# RTC_ds1307z.net
KiCad netlist of a schematic drawn in Altium Designer
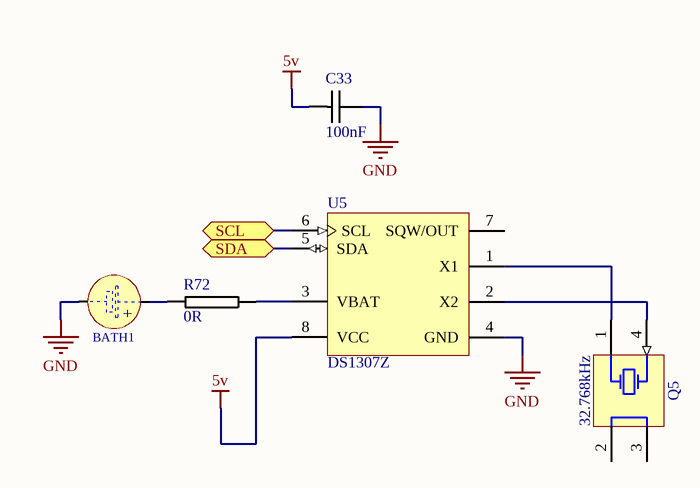
[diagram p0: RTC_ds1307z.SchDoc]

(export (version "E")
  (design (tool "Eeschema 10.0.6"))
  (components
    (comp (ref "BATH1")
      (value "~")
      (footprint "BATH_KEYSTONE_103")
      (description "Battery Holder whit 2 Pin")
      (fields
        (field (name "PART NUMBER") "BATH_KEYSTONE_103")
        (field (name "MANUFACTURER") "KEYSTONE")
        (field (name "AUTHOR") "CERN DEM JLC")
      )
      (libsource (lib "Eletro-mechanical") (part "Battery Holder 2 Pin"))
    )
    (comp (ref "C33")
      (value "100nF")
      (footprint "0805C-TBD")
      (description "CAPACITOR 0805 CERAMIC")
      (libsource (lib "vh_altium_library") (part "0805C-100nF-25V-X7R-MUR"))
    )
    (comp (ref "Q5")
      (value "32.768kHz")
      (footprint "XTAL_EPSON_MC-406")
      (description "Crystal 4 pins 1=XTAL Control 2 And 3=NC 4=XTAL")
      (fields
        (field (name "PART NUMBER") "XTAL_32.768KHZ_EPSON_MC-406 32.768K-A3:ROHS")
        (field (name "MANUFACTURER") "EPSON TOYOCOM")
        (field (name "AUTHOR") "CERN DEM JLC")
      )
      (libsource (lib "ICs And Semiconductors") (part "Quartz Crystal 1X 2-3NC 4X"))
    )
    (comp (ref "R72")
      (value "0R")
      (footprint "0805R-GENERIC")
      (description "RESISTOR 0805 1 WATT")
      (libsource (lib "vh_altium_library") (part "0805R-0R"))
    )
    (comp (ref "U5")
      (value "DS1307Z")
      (footprint "S8-2_N")
      (description "64 x 8, Serial, I2C Real-Time Clock, 5.0V, 8-Pin SO, 0 to 70 degC")
      (libsource (lib "Maxim Real-Time Clocks (RTCs)") (part "DS1307Z"))
    )
  )
  (nets
    (net (code "1") (name "/SCL") (class "Default")
      (node (ref "U5") (pin "6") (pinfunction "SCL_6") (pintype "input"))
    )
    (net (code "2") (name "/SDA") (class "Default")
      (node (ref "U5") (pin "5") (pinfunction "SDA_5") (pintype "bidirectional"))
    )
    (net (code "3") (name "5v") (class "Default")
      (node (ref "C33") (pin "1") (pintype "passive"))
      (node (ref "U5") (pin "8") (pinfunction "VCC_8") (pintype "power_in"))
    )
    (net (code "4") (name "GND") (class "Default")
      (node (ref "BATH1") (pin "2") (pinfunction "MINUS_2") (pintype "power_in"))
      (node (ref "C33") (pin "2") (pintype "passive"))
      (node (ref "U5") (pin "4") (pinfunction "GND_4") (pintype "power_in"))
    )
    (net (code "5") (name "Net-(BATH1-PLUS)") (class "Default")
      (node (ref "BATH1") (pin "1") (pinfunction "PLUS_1") (pintype "power_in"))
      (node (ref "R72") (pin "1") (pintype "passive"))
    )
    (net (code "6") (name "Net-(U5-VBAT)") (class "Default")
      (node (ref "R72") (pin "2") (pintype "passive"))
      (node (ref "U5") (pin "3") (pinfunction "VBAT_3") (pintype "power_in"))
    )
    (net (code "7") (name "Net-(U5-X1)") (class "Default")
      (node (ref "Q5") (pin "1") (pinfunction "X_1") (pintype "power_in"))
      (node (ref "U5") (pin "1") (pinfunction "X1_1") (pintype "passive"))
    )
    (net (code "8") (name "Net-(U5-X2)") (class "Default")
      (node (ref "Q5") (pin "4") (pinfunction "X_4") (pintype "input"))
      (node (ref "U5") (pin "2") (pinfunction "X2_2") (pintype "passive"))
    )
    (net (code "9") (name "unconnected-(Q5-GND-Pad2)") (class "Default")
      (node (ref "Q5") (pin "2") (pinfunction "GND_2") (pintype "power_in"))
    )
    (net (code "10") (name "unconnected-(Q5-GND-Pad3)") (class "Default")
      (node (ref "Q5") (pin "3") (pinfunction "GND_3") (pintype "power_in"))
    )
    (net (code "11") (name "unconnected-(U5-SQW{slash}OUT-Pad7)") (class "Default")
      (node (ref "U5") (pin "7") (pinfunction "SQW/OUT_7") (pintype "open_collector"))
    )
  )
)
